# LRA_FlightComputerV.net
KiCad netlist of a schematic drawn in EAGLE
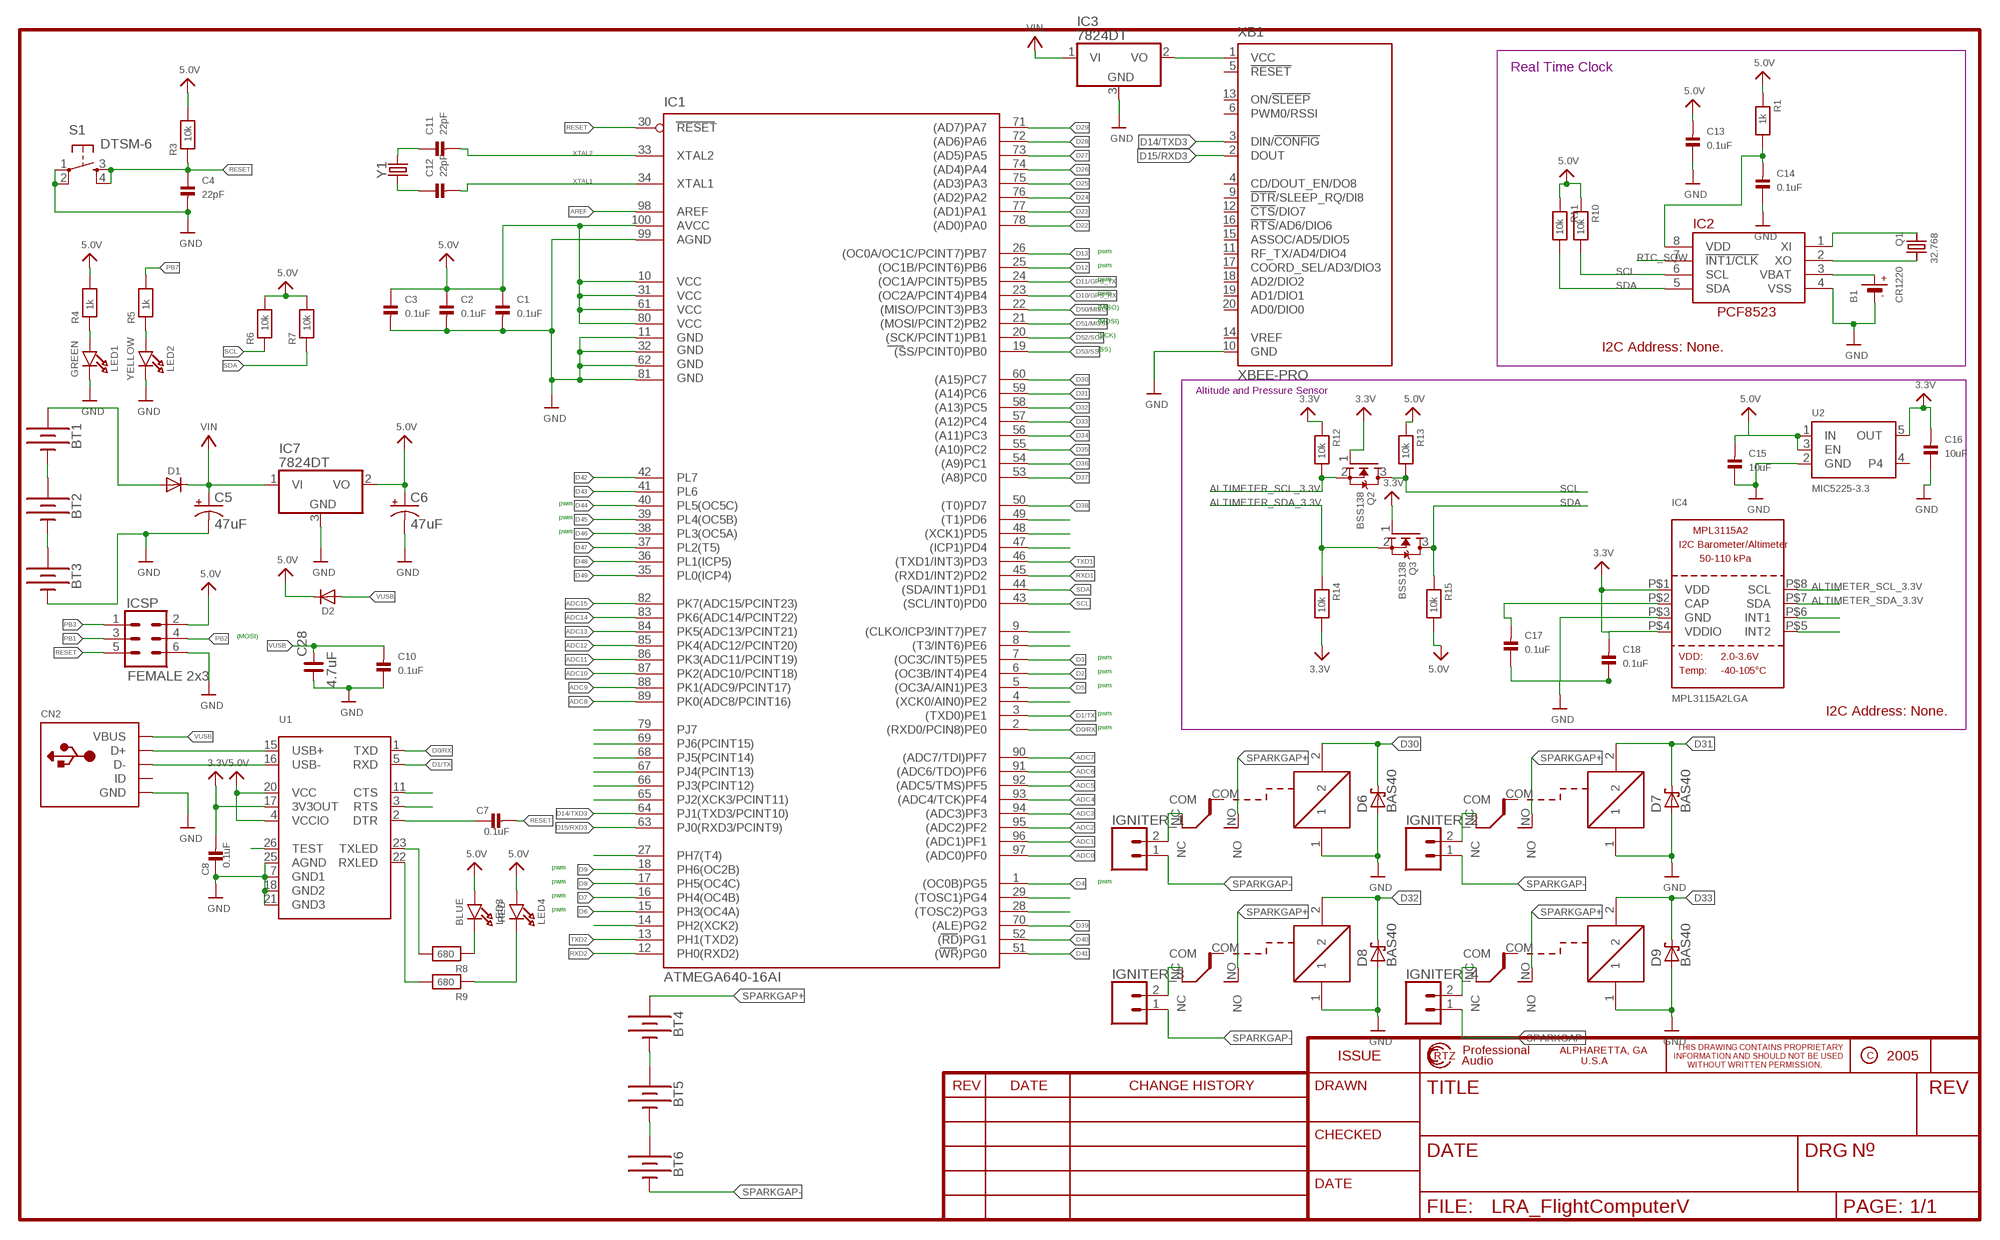
[diagram p0: schematic, sheet 1, part 1 of 2]
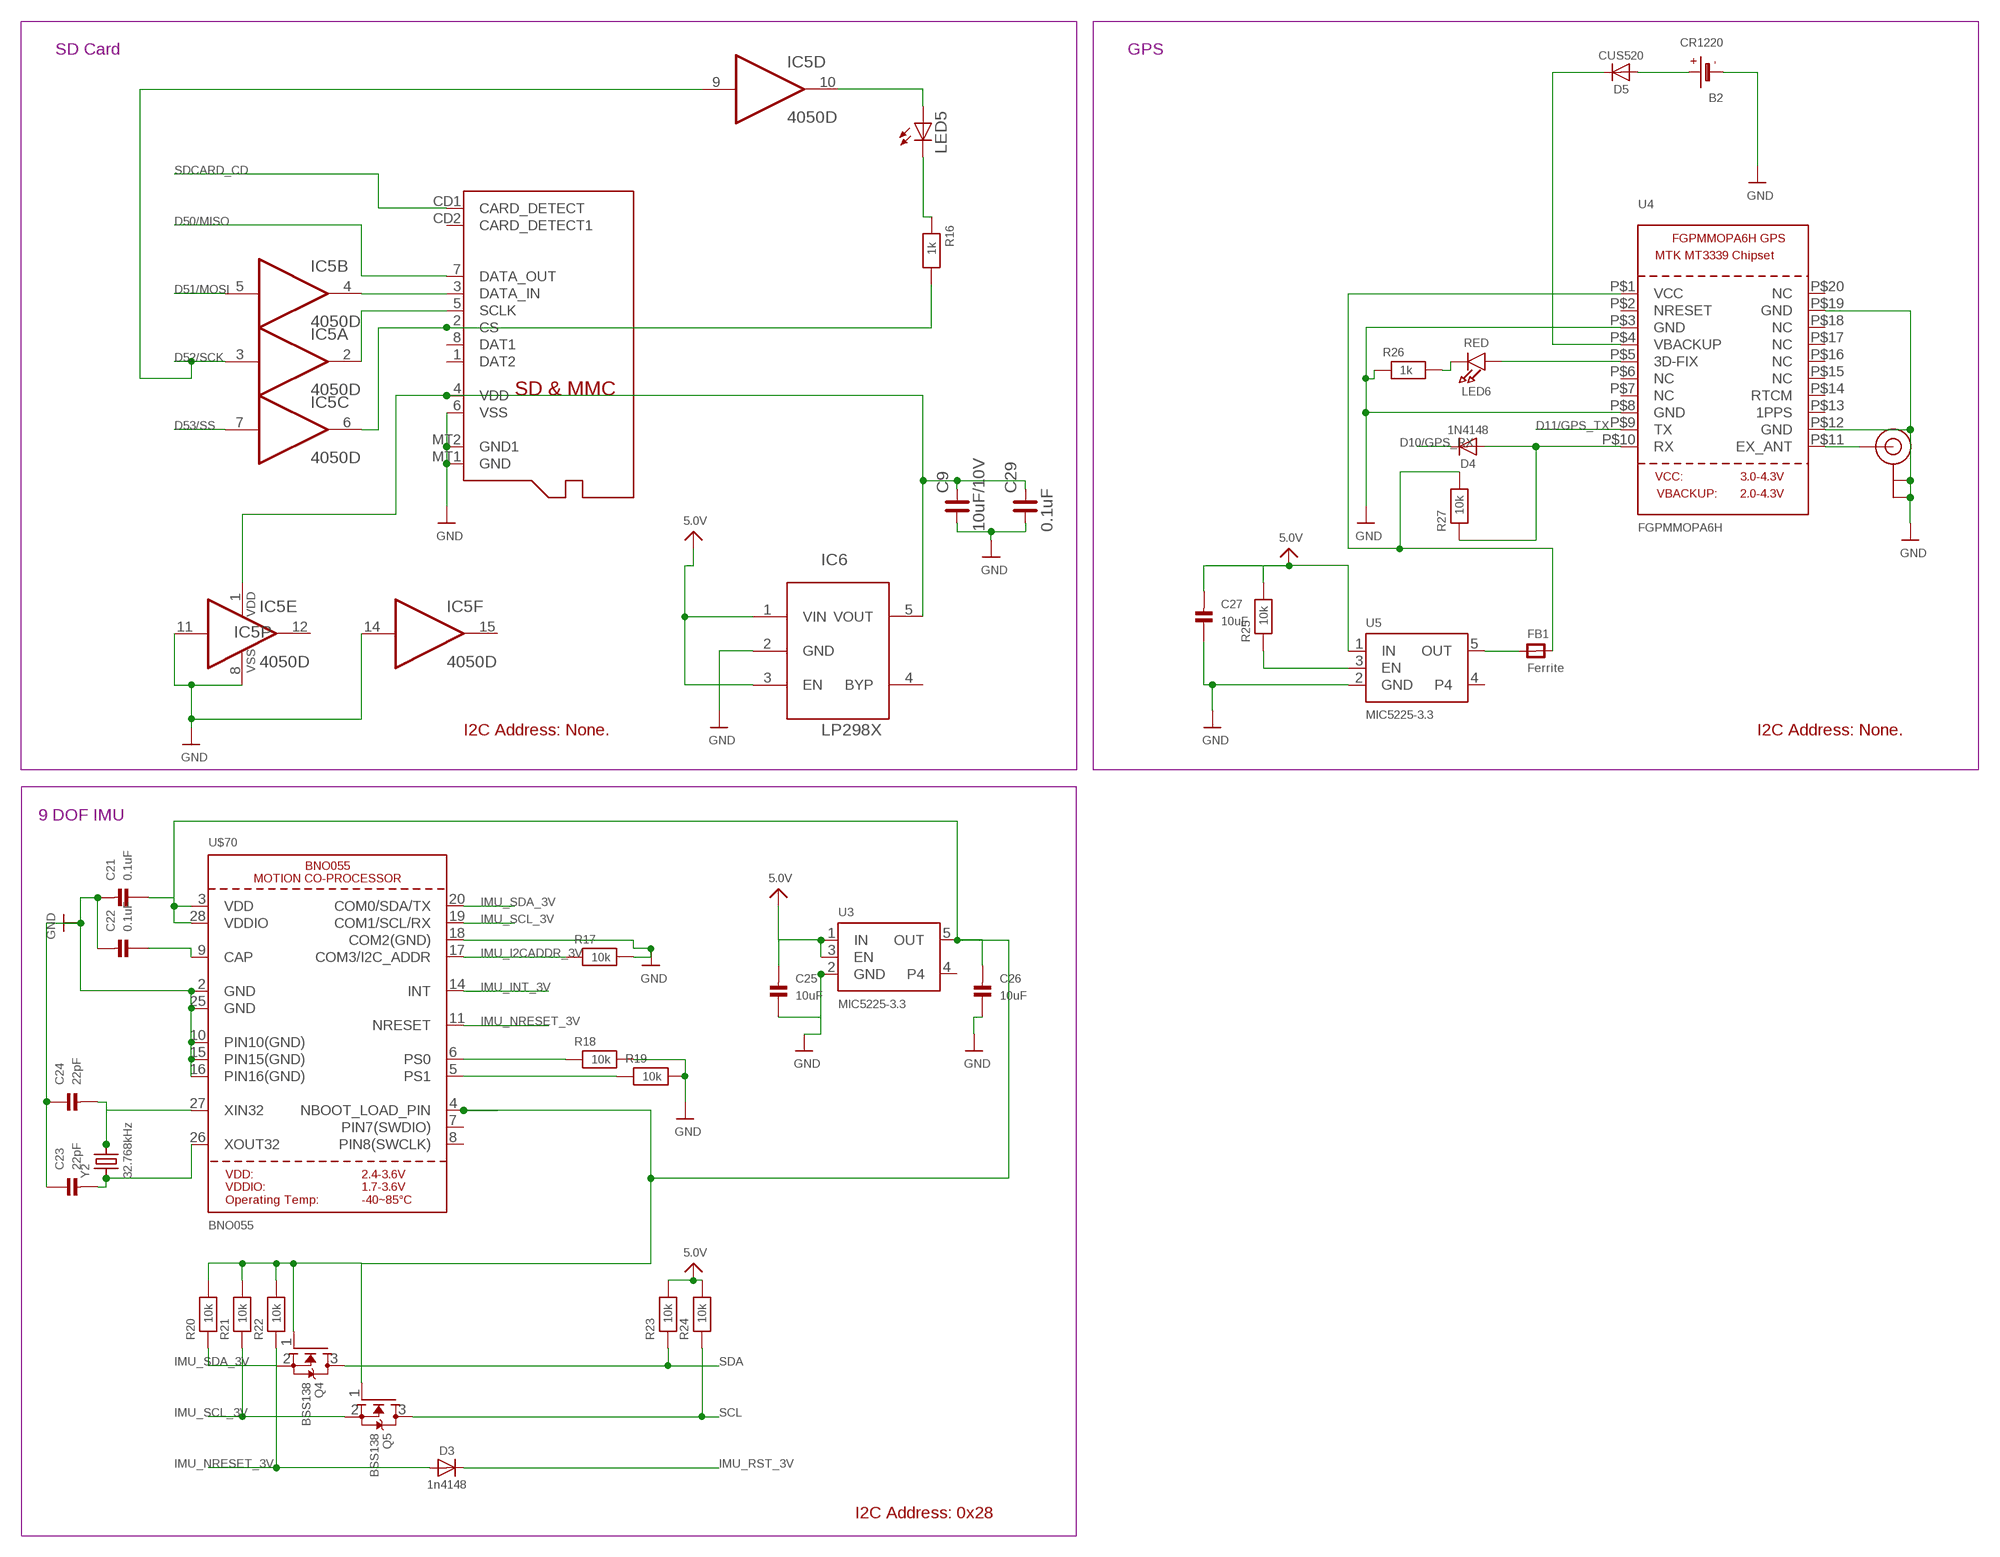
[diagram p1: schematic, sheet 1, part 2 of 2]

(export (version "E")
  (design (tool "Eeschema 10.0.6"))
  (components
    (comp (ref "B1")
      (value "CR1220")
      (footprint "eagle-import:CR1220")
      (libsource (lib "eagle-import") (part "BATTERYCR1220_SMT"))
    )
    (comp (ref "B2")
      (value "CR1220")
      (footprint "eagle-import:CR1220")
      (libsource (lib "eagle-import") (part "BATTERYCR1220_SMT"))
    )
    (comp (ref "BT1")
      (value "BATTERY-18650")
      (footprint "eagle-import:BATTERY_18650-HOLDER")
      (libsource (lib "eagle-import") (part "BATTERY-18650"))
    )
    (comp (ref "BT2")
      (value "BATTERY-18650")
      (footprint "eagle-import:BATTERY_18650-HOLDER")
      (libsource (lib "eagle-import") (part "BATTERY-18650"))
    )
    (comp (ref "BT3")
      (value "BATTERY-18650")
      (footprint "eagle-import:BATTERY_18650-HOLDER")
      (libsource (lib "eagle-import") (part "BATTERY-18650"))
    )
    (comp (ref "BT4")
      (value "BATTERY-18650")
      (footprint "eagle-import:BATTERY_18650-HOLDER")
      (libsource (lib "eagle-import") (part "BATTERY-18650"))
    )
    (comp (ref "BT5")
      (value "BATTERY-18650")
      (footprint "eagle-import:BATTERY_18650-HOLDER")
      (libsource (lib "eagle-import") (part "BATTERY-18650"))
    )
    (comp (ref "BT6")
      (value "BATTERY-18650")
      (footprint "eagle-import:BATTERY_18650-HOLDER")
      (libsource (lib "eagle-import") (part "BATTERY-18650"))
    )
    (comp (ref "C1")
      (value "0.1uF")
      (footprint "eagle-import:0805@1")
      (libsource (lib "eagle-import") (part "CAP_CERAMIC0805"))
    )
    (comp (ref "C2")
      (value "0.1uF")
      (footprint "eagle-import:0805@1")
      (libsource (lib "eagle-import") (part "CAP_CERAMIC0805"))
    )
    (comp (ref "C3")
      (value "0.1uF")
      (footprint "eagle-import:0805@1")
      (libsource (lib "eagle-import") (part "CAP_CERAMIC0805"))
    )
    (comp (ref "C4")
      (value "22pF")
      (footprint "eagle-import:0805@1")
      (libsource (lib "eagle-import") (part "CAP_CERAMIC0805"))
    )
    (comp (ref "C5")
      (value "47uF")
      (footprint "eagle-import:PANASONIC_D")
      (libsource (lib "eagle-import") (part "CPOL-USD"))
    )
    (comp (ref "C6")
      (value "47uF")
      (footprint "eagle-import:PANASONIC_D")
      (libsource (lib "eagle-import") (part "CPOL-USD"))
    )
    (comp (ref "C7")
      (value "0.1uF")
      (footprint "eagle-import:0805@1")
      (libsource (lib "eagle-import") (part "CAP_CERAMIC0805"))
    )
    (comp (ref "C8")
      (value "0.1uF")
      (footprint "eagle-import:0805@1")
      (libsource (lib "eagle-import") (part "CAP_CERAMIC0805"))
    )
    (comp (ref "C9")
      (value "10uF/10V")
      (footprint "eagle-import:C0805")
      (libsource (lib "eagle-import") (part "C_0805"))
    )
    (comp (ref "C10")
      (value "0.1uF")
      (footprint "eagle-import:0805@1")
      (libsource (lib "eagle-import") (part "CAP_CERAMIC0805"))
    )
    (comp (ref "C11")
      (value "22pF")
      (footprint "eagle-import:0805@1")
      (libsource (lib "eagle-import") (part "CAP_CERAMIC0805"))
    )
    (comp (ref "C12")
      (value "22pF")
      (footprint "eagle-import:0805@1")
      (libsource (lib "eagle-import") (part "CAP_CERAMIC0805"))
    )
    (comp (ref "C13")
      (value "0.1uF")
      (footprint "eagle-import:0805@1")
      (libsource (lib "eagle-import") (part "CAP_CERAMIC0805"))
    )
    (comp (ref "C14")
      (value "0.1uF")
      (footprint "eagle-import:0805@1")
      (libsource (lib "eagle-import") (part "CAP_CERAMIC0805"))
    )
    (comp (ref "C15")
      (value "10uF")
      (footprint "eagle-import:0805@1")
      (libsource (lib "eagle-import") (part "CAP_CERAMIC0805"))
    )
    (comp (ref "C16")
      (value "10uF")
      (footprint "eagle-import:0805@1")
      (libsource (lib "eagle-import") (part "CAP_CERAMIC0805"))
    )
    (comp (ref "C17")
      (value "0.1uF")
      (footprint "eagle-import:0805@1")
      (libsource (lib "eagle-import") (part "CAP_CERAMIC0805"))
    )
    (comp (ref "C18")
      (value "0.1uF")
      (footprint "eagle-import:0805@1")
      (libsource (lib "eagle-import") (part "CAP_CERAMIC0805"))
    )
    (comp (ref "C21")
      (value "0.1uF")
      (footprint "eagle-import:0805@1")
      (libsource (lib "eagle-import") (part "CAP_CERAMIC0805"))
    )
    (comp (ref "C22")
      (value "0.1uF")
      (footprint "eagle-import:0805@1")
      (libsource (lib "eagle-import") (part "CAP_CERAMIC0805"))
    )
    (comp (ref "C23")
      (value "22pF")
      (footprint "eagle-import:0805@1")
      (libsource (lib "eagle-import") (part "CAP_CERAMIC0805"))
    )
    (comp (ref "C24")
      (value "22pF")
      (footprint "eagle-import:0805@1")
      (libsource (lib "eagle-import") (part "CAP_CERAMIC0805"))
    )
    (comp (ref "C25")
      (value "10uF")
      (footprint "eagle-import:0805@1")
      (libsource (lib "eagle-import") (part "CAP_CERAMIC0805"))
    )
    (comp (ref "C26")
      (value "10uF")
      (footprint "eagle-import:0805@1")
      (libsource (lib "eagle-import") (part "CAP_CERAMIC0805"))
    )
    (comp (ref "C27")
      (value "10uF")
      (footprint "eagle-import:0805@1")
      (libsource (lib "eagle-import") (part "CAP_CERAMIC0805"))
    )
    (comp (ref "C28")
      (value "4.7uF")
      (footprint "eagle-import:C0805")
      (libsource (lib "eagle-import") (part "C_0805"))
    )
    (comp (ref "C29")
      (value "0.1uF")
      (footprint "eagle-import:C0805")
      (libsource (lib "eagle-import") (part "C_0805"))
    )
    (comp (ref "CN2")
      (value "USBMINIB")
      (footprint "eagle-import:USB-MINIB")
      (libsource (lib "eagle-import") (part "USBMINIB"))
    )
    (comp (ref "D1")
      (value "DIODESOD-123")
      (footprint "eagle-import:SOD-123")
      (libsource (lib "eagle-import") (part "DIODESOD-123"))
    )
    (comp (ref "D2")
      (value "DIODESOD-123")
      (footprint "eagle-import:SOD-123")
      (libsource (lib "eagle-import") (part "DIODESOD-123"))
    )
    (comp (ref "D3")
      (value "1n4148")
      (footprint "eagle-import:SOD-323")
      (libsource (lib "eagle-import") (part "DIODESOD-323"))
    )
    (comp (ref "D4")
      (value "1N4148")
      (footprint "eagle-import:SOD-323")
      (libsource (lib "eagle-import") (part "DIODESOD-323"))
    )
    (comp (ref "D5")
      (value "CUS520")
      (footprint "eagle-import:SOD-323")
      (libsource (lib "eagle-import") (part "DIODESOD-323"))
    )
    (comp (ref "D6")
      (value "BAS40")
      (footprint "eagle-import:SOT23")
      (libsource (lib "eagle-import") (part "BAS40"))
    )
    (comp (ref "D7")
      (value "BAS40")
      (footprint "eagle-import:SOT23")
      (libsource (lib "eagle-import") (part "BAS40"))
    )
    (comp (ref "D8")
      (value "BAS40")
      (footprint "eagle-import:SOT23")
      (libsource (lib "eagle-import") (part "BAS40"))
    )
    (comp (ref "D9")
      (value "BAS40")
      (footprint "eagle-import:SOT23")
      (libsource (lib "eagle-import") (part "BAS40"))
    )
    (comp (ref "FB1")
      (value "Ferrite")
      (footprint "eagle-import:0805-NO")
      (libsource (lib "eagle-import") (part "FERRITE-0805NO"))
    )
    (comp (ref "IC1")
      (value "ATMEGA640-16AI")
      (footprint "eagle-import:TQFP100")
      (libsource (lib "eagle-import") (part "ATMEGAAI640-16"))
    )
    (comp (ref "IC2")
      (value "RTC_PCF8523T")
      (footprint "eagle-import:SOIC8_150MIL")
      (libsource (lib "eagle-import") (part "RTC_PCF8523T"))
    )
    (comp (ref "IC3")
      (value "7824DT")
      (footprint "eagle-import:TO252")
      (libsource (lib "eagle-import") (part "78DT24"))
    )
    (comp (ref "IC4")
      (value "MPL3115A2LGA")
      (footprint "eagle-import:LGA8")
      (libsource (lib "eagle-import") (part "MPL3115A2LGA"))
    )
    (comp (ref "IC5")
      (value "4050D")
      (footprint "eagle-import:SO16")
      (libsource (lib "eagle-import") (part "4050D"))
    )
    (comp (ref "IC6")
      (value "LP298XS")
      (footprint "eagle-import:SOT23-5L")
      (libsource (lib "eagle-import") (part "LP298XS"))
    )
    (comp (ref "IC7")
      (value "7824DT")
      (footprint "eagle-import:TO252")
      (libsource (lib "eagle-import") (part "78DT24"))
    )
    (comp (ref "ICSP")
      (value "FEMALE 2x3")
      (footprint "eagle-import:2X3")
      (libsource (lib "eagle-import") (part "CONN_03X2FEMALE"))
    )
    (comp (ref "IGNITER_1")
      (value "CONN_02")
      (footprint "eagle-import:1X02")
      (libsource (lib "eagle-import") (part "CONN_02"))
    )
    (comp (ref "IGNITER_2")
      (value "CONN_02")
      (footprint "eagle-import:1X02")
      (libsource (lib "eagle-import") (part "CONN_02"))
    )
    (comp (ref "IGNITER_3")
      (value "CONN_02")
      (footprint "eagle-import:1X02")
      (libsource (lib "eagle-import") (part "CONN_02"))
    )
    (comp (ref "IGNITER_4")
      (value "CONN_02")
      (footprint "eagle-import:1X02")
      (libsource (lib "eagle-import") (part "CONN_02"))
    )
    (comp (ref "LED1")
      (value "GREEN")
      (footprint "eagle-import:CHIPLED_0805")
      (libsource (lib "eagle-import") (part "LED0805"))
    )
    (comp (ref "LED2")
      (value "YELLOW")
      (footprint "eagle-import:CHIPLED_0805")
      (libsource (lib "eagle-import") (part "LED0805"))
    )
    (comp (ref "LED3")
      (value "BLUE")
      (footprint "eagle-import:CHIPLED_0805")
      (libsource (lib "eagle-import") (part "LED0805"))
    )
    (comp (ref "LED4")
      (value "RED")
      (footprint "eagle-import:CHIPLED_0805")
      (libsource (lib "eagle-import") (part "LED0805"))
    )
    (comp (ref "LED5")
      (value "LEDCHIPLED_0805")
      (footprint "eagle-import:CHIPLED_0805")
      (libsource (lib "eagle-import") (part "LEDCHIPLED_0805"))
    )
    (comp (ref "LED6")
      (value "RED")
      (footprint "eagle-import:CHIPLED_0805")
      (libsource (lib "eagle-import") (part "LED0805"))
    )
    (comp (ref "Q1")
      (value "32.768")
      (footprint "eagle-import:CRYSTAL_8X3.8")
      (libsource (lib "eagle-import") (part "CRYSTAL8.0X3.8"))
    )
    (comp (ref "Q2")
      (value "BSS138")
      (footprint "eagle-import:SOT23-WIDE")
      (libsource (lib "eagle-import") (part "MOSFET-NWIDE"))
    )
    (comp (ref "Q3")
      (value "BSS138")
      (footprint "eagle-import:SOT23-WIDE")
      (libsource (lib "eagle-import") (part "MOSFET-NWIDE"))
    )
    (comp (ref "Q4")
      (value "BSS138")
      (footprint "eagle-import:SOT23-WIDE")
      (libsource (lib "eagle-import") (part "MOSFET-NWIDE"))
    )
    (comp (ref "Q5")
      (value "BSS138")
      (footprint "eagle-import:SOT23-WIDE")
      (libsource (lib "eagle-import") (part "MOSFET-NWIDE"))
    )
    (comp (ref "R1")
      (value "1k")
      (footprint "eagle-import:0805@1")
      (libsource (lib "eagle-import") (part "RESISTOR0805"))
    )
    (comp (ref "R3")
      (value "10k")
      (footprint "eagle-import:0805@1")
      (libsource (lib "eagle-import") (part "RESISTOR0805"))
    )
    (comp (ref "R4")
      (value "1k")
      (footprint "eagle-import:0805@1")
      (libsource (lib "eagle-import") (part "RESISTOR0805"))
    )
    (comp (ref "R5")
      (value "1k")
      (footprint "eagle-import:0805@1")
      (libsource (lib "eagle-import") (part "RESISTOR0805"))
    )
    (comp (ref "R6")
      (value "10k")
      (footprint "eagle-import:0805@1")
      (libsource (lib "eagle-import") (part "RESISTOR0805"))
    )
    (comp (ref "R7")
      (value "10k")
      (footprint "eagle-import:0805@1")
      (libsource (lib "eagle-import") (part "RESISTOR0805"))
    )
    (comp (ref "R8")
      (value "680")
      (footprint "eagle-import:0805@1")
      (libsource (lib "eagle-import") (part "RESISTOR0805"))
    )
    (comp (ref "R9")
      (value "680")
      (footprint "eagle-import:0805@1")
      (libsource (lib "eagle-import") (part "RESISTOR0805"))
    )
    (comp (ref "R10")
      (value "10k")
      (footprint "eagle-import:0805@1")
      (libsource (lib "eagle-import") (part "RESISTOR0805"))
    )
    (comp (ref "R11")
      (value "10k")
      (footprint "eagle-import:0805@1")
      (libsource (lib "eagle-import") (part "RESISTOR0805"))
    )
    (comp (ref "R12")
      (value "10k")
      (footprint "eagle-import:0805@1")
      (libsource (lib "eagle-import") (part "RESISTOR0805"))
    )
    (comp (ref "R13")
      (value "10k")
      (footprint "eagle-import:0805@1")
      (libsource (lib "eagle-import") (part "RESISTOR0805"))
    )
    (comp (ref "R14")
      (value "10k")
      (footprint "eagle-import:0805@1")
      (libsource (lib "eagle-import") (part "RESISTOR0805"))
    )
    (comp (ref "R15")
      (value "10k")
      (footprint "eagle-import:0805@1")
      (libsource (lib "eagle-import") (part "RESISTOR0805"))
    )
    (comp (ref "R16")
      (value "1k")
      (footprint "eagle-import:0805@1")
      (libsource (lib "eagle-import") (part "RESISTOR0805"))
    )
    (comp (ref "R17")
      (value "10k")
      (footprint "eagle-import:0805@1")
      (libsource (lib "eagle-import") (part "RESISTOR0805"))
    )
    (comp (ref "R18")
      (value "10k")
      (footprint "eagle-import:0805@1")
      (libsource (lib "eagle-import") (part "RESISTOR0805"))
    )
    (comp (ref "R19")
      (value "10k")
      (footprint "eagle-import:0805@1")
      (libsource (lib "eagle-import") (part "RESISTOR0805"))
    )
    (comp (ref "R20")
      (value "10k")
      (footprint "eagle-import:0805@1")
      (libsource (lib "eagle-import") (part "RESISTOR0805"))
    )
    (comp (ref "R21")
      (value "10k")
      (footprint "eagle-import:0805@1")
      (libsource (lib "eagle-import") (part "RESISTOR0805"))
    )
    (comp (ref "R22")
      (value "10k")
      (footprint "eagle-import:0805@1")
      (libsource (lib "eagle-import") (part "RESISTOR0805"))
    )
    (comp (ref "R23")
      (value "10k")
      (footprint "eagle-import:0805@1")
      (libsource (lib "eagle-import") (part "RESISTOR0805"))
    )
    (comp (ref "R24")
      (value "10k")
      (footprint "eagle-import:0805@1")
      (libsource (lib "eagle-import") (part "RESISTOR0805"))
    )
    (comp (ref "R25")
      (value "10k")
      (footprint "eagle-import:0805@1")
      (libsource (lib "eagle-import") (part "RESISTOR0805"))
    )
    (comp (ref "R26")
      (value "1k")
      (footprint "eagle-import:0805@1")
      (libsource (lib "eagle-import") (part "RESISTOR0805"))
    )
    (comp (ref "R27")
      (value "10k")
      (footprint "eagle-import:0805@1")
      (libsource (lib "eagle-import") (part "RESISTOR0805"))
    )
    (comp (ref "S1")
      (value "DTSM-6")
      (footprint "eagle-import:DTSM-6")
      (libsource (lib "eagle-import") (part "DTSM-6"))
    )
    (comp (ref "U$70")
      (value "BNO055")
      (footprint "eagle-import:BNO055")
      (libsource (lib "eagle-import") (part "BNO055"))
    )
    (comp (ref "U$78")
      (value "U.FL")
      (footprint "eagle-import:U.FL")
      (libsource (lib "eagle-import") (part "U.FL"))
    )
    (comp (ref "U$84")
      (value "RW-SH")
      (footprint "eagle-import:RW-SH")
      (libsource (lib "eagle-import") (part "RW-SH"))
    )
    (comp (ref "U$86")
      (value "RW-SH")
      (footprint "eagle-import:RW-SH")
      (libsource (lib "eagle-import") (part "RW-SH"))
    )
    (comp (ref "U$87")
      (value "RW-SH")
      (footprint "eagle-import:RW-SH")
      (libsource (lib "eagle-import") (part "RW-SH"))
    )
    (comp (ref "U$90")
      (value "RW-SH")
      (footprint "eagle-import:RW-SH")
      (libsource (lib "eagle-import") (part "RW-SH"))
    )
    (comp (ref "U1")
      (value "FT232RLSSOP28")
      (footprint "eagle-import:SSOP28DB")
      (libsource (lib "eagle-import") (part "FT232RLSSOP28"))
    )
    (comp (ref "U2")
      (value "MIC5225-3.3")
      (footprint "eagle-import:SOT23-5")
      (libsource (lib "eagle-import") (part "VREG_SOT23-5"))
    )
    (comp (ref "U3")
      (value "MIC5225-3.3")
      (footprint "eagle-import:SOT23-5")
      (libsource (lib "eagle-import") (part "VREG_SOT23-5"))
    )
    (comp (ref "U4")
      (value "FGPMMOPA6H")
      (footprint "eagle-import:FGPMMOPA6H")
      (libsource (lib "eagle-import") (part "GPS_FGPMMOPA6H"))
    )
    (comp (ref "U5")
      (value "MIC5225-3.3")
      (footprint "eagle-import:SOT23-5")
      (libsource (lib "eagle-import") (part "VREG_SOT23-5"))
    )
    (comp (ref "X1")
      (value "MICROSD")
      (footprint "eagle-import:MICROSD")
      (libsource (lib "eagle-import") (part "MICROSD"))
    )
    (comp (ref "XB1")
      (value "XBEE-PRO")
      (footprint "eagle-import:XBEE-PRO")
      (fields (field (name "MPN") "XBP24-AWI-001"))
      (libsource (lib "eagle-import") (part "XBEE-PRO"))
    )
    (comp (ref "Y1")
      (value "CRYSTALPTH-HC49US")
      (footprint "eagle-import:HC49US")
      (libsource (lib "eagle-import") (part "CRYSTALPTH-HC49US"))
    )
    (comp (ref "Y2")
      (value "32.768kHz")
      (footprint "eagle-import:CRYSTAL_8X3.8")
      (libsource (lib "eagle-import") (part "CRYSTAL8.0X3.8"))
    )
  )
  (nets
    (net (code "1") (name "/ALTIMETER_SCL_3.3V") (class "Default")
      (node (ref "IC4") (pin "P$8") (pinfunction "SCL_P$8") (pintype "bidirectional"))
      (node (ref "Q2") (pin "2") (pinfunction "S_2") (pintype "bidirectional"))
      (node (ref "R12") (pin "2") (pinfunction "2_2") (pintype "passive"))
    )
    (net (code "2") (name "/ALTIMETER_SDA_3.3V") (class "Default")
      (node (ref "IC4") (pin "P$7") (pinfunction "SDA_P$7") (pintype "bidirectional"))
      (node (ref "Q3") (pin "2") (pinfunction "S_2") (pintype "bidirectional"))
      (node (ref "R14") (pin "1") (pinfunction "1_1") (pintype "passive"))
    )
    (net (code "3") (name "/IMU_I2CADDR_3V") (class "Default")
      (node (ref "R17") (pin "1") (pinfunction "1_1") (pintype "passive"))
      (node (ref "U$70") (pin "17") (pinfunction "COM3/I2C_ADDR_17") (pintype "bidirectional"))
    )
    (net (code "4") (name "/IMU_INT_3V") (class "Default")
      (node (ref "U$70") (pin "14") (pinfunction "INT_14") (pintype "output"))
    )
    (net (code "5") (name "/IMU_NRESET_3V") (class "Default")
      (node (ref "D3") (pin "A") (pinfunction "A_A") (pintype "passive"))
      (node (ref "R22") (pin "1") (pinfunction "1_1") (pintype "passive"))
      (node (ref "U$70") (pin "11") (pinfunction "NRESET_11") (pintype "bidirectional"))
    )
    (net (code "6") (name "/IMU_RST_3V") (class "Default")
      (node (ref "D3") (pin "C") (pinfunction "C_C") (pintype "passive"))
    )
    (net (code "7") (name "/IMU_SCL_3V") (class "Default")
      (node (ref "Q5") (pin "2") (pinfunction "S_2") (pintype "bidirectional"))
      (node (ref "R21") (pin "1") (pinfunction "1_1") (pintype "passive"))
      (node (ref "U$70") (pin "19") (pinfunction "COM1/SCL/RX_19") (pintype "bidirectional"))
    )
    (net (code "8") (name "/IMU_SDA_3V") (class "Default")
      (node (ref "Q4") (pin "2") (pinfunction "S_2") (pintype "bidirectional"))
      (node (ref "R20") (pin "1") (pinfunction "1_1") (pintype "passive"))
      (node (ref "U$70") (pin "20") (pinfunction "COM0/SDA/TX_20") (pintype "bidirectional"))
    )
    (net (code "9") (name "/OUT") (class "Default")
      (node (ref "C21") (pin "1") (pinfunction "P$1_1") (pintype "passive"))
      (node (ref "C26") (pin "2") (pinfunction "P$2_2") (pintype "passive"))
      (node (ref "FB1") (pin "1") (pinfunction "P$1_1") (pintype "passive"))
      (node (ref "Q4") (pin "1") (pinfunction "G_1") (pintype "bidirectional"))
      (node (ref "Q5") (pin "1") (pinfunction "G_1") (pintype "bidirectional"))
      (node (ref "R20") (pin "2") (pinfunction "2_2") (pintype "passive"))
      (node (ref "R21") (pin "2") (pinfunction "2_2") (pintype "passive"))
      (node (ref "R22") (pin "2") (pinfunction "2_2") (pintype "passive"))
      (node (ref "U$70") (pin "28") (pinfunction "VDDIO_28") (pintype "power_in"))
      (node (ref "U$70") (pin "3") (pinfunction "VDD_3") (pintype "power_in"))
      (node (ref "U$70") (pin "4") (pinfunction "NBOOT_LOAD_PIN_4") (pintype "bidirectional"))
      (node (ref "U3") (pin "5") (pinfunction "OUT_5") (pintype "power_in"))
      (node (ref "U5") (pin "5") (pinfunction "OUT_5") (pintype "power_in"))
    )
    (net (code "10") (name "/RTC_SQW") (class "Default")
      (node (ref "IC2") (pin "7") (pinfunction "~{INT1/CLK}_7") (pintype "output"))
    )
    (net (code "11") (name "/SDCARD_CD") (class "Default")
      (node (ref "X1") (pin "CD1") (pinfunction "CARD_DETECT_CD1") (pintype "passive"))
    )
    (net (code "12") (name "/XTAL1") (class "Default")
      (node (ref "C12") (pin "2") (pinfunction "P$2_2") (pintype "passive"))
      (node (ref "IC1") (pin "34") (pinfunction "XTAL1_34") (pintype "input"))
    )
    (net (code "13") (name "/XTAL2") (class "Default")
      (node (ref "C11") (pin "2") (pinfunction "P$2_2") (pintype "passive"))
      (node (ref "IC1") (pin "33") (pinfunction "XTAL2_33") (pintype "output"))
    )
    (net (code "14") (name "3.3V") (class "Default")
      (node (ref "C16") (pin "2") (pinfunction "P$2_2") (pintype "passive"))
      (node (ref "C18") (pin "2") (pinfunction "P$2_2") (pintype "passive"))
      (node (ref "C8") (pin "2") (pinfunction "P$2_2") (pintype "passive"))
      (node (ref "IC4") (pin "P$1") (pinfunction "VDD_P$1") (pintype "power_in"))
      (node (ref "IC4") (pin "P$4") (pinfunction "VDDIO_P$4") (pintype "power_in"))
      (node (ref "Q2") (pin "1") (pinfunction "G_1") (pintype "bidirectional"))
      (node (ref "Q3") (pin "1") (pinfunction "G_1") (pintype "bidirectional"))
      (node (ref "R12") (pin "1") (pinfunction "1_1") (pintype "passive"))
      (node (ref "R14") (pin "2") (pinfunction "2_2") (pintype "passive"))
      (node (ref "U1") (pin "17") (pinfunction "3V3OUT_17") (pintype "power_in"))
      (node (ref "U2") (pin "5") (pinfunction "OUT_5") (pintype "power_in"))
    )
    (net (code "15") (name "5.0V") (class "Default")
      (node (ref "C1") (pin "1") (pinfunction "P$1_1") (pintype "passive"))
      (node (ref "C13") (pin "2") (pinfunction "P$2_2") (pintype "passive"))
      (node (ref "C15") (pin "2") (pinfunction "P$2_2") (pintype "passive"))
      (node (ref "C2") (pin "1") (pinfunction "P$1_1") (pintype "passive"))
      (node (ref "C25") (pin "2") (pinfunction "P$2_2") (pintype "passive"))
      (node (ref "C27") (pin "2") (pinfunction "P$2_2") (pintype "passive"))
      (node (ref "C3") (pin "1") (pinfunction "P$1_1") (pintype "passive"))
      (node (ref "C6") (pin "+") (pinfunction "+_+") (pintype "passive"))
      (node (ref "D2") (pin "C") (pinfunction "C_C") (pintype "passive"))
      (node (ref "IC1") (pin "10") (pinfunction "VCC_10") (pintype "power_in"))
      (node (ref "IC1") (pin "100") (pinfunction "AVCC_100") (pintype "power_in"))
      (node (ref "IC1") (pin "31") (pinfunction "VCC1_31") (pintype "power_in"))
      (node (ref "IC1") (pin "61") (pinfunction "VCC2_61") (pintype "power_in"))
      (node (ref "IC1") (pin "80") (pinfunction "VCC3_80") (pintype "power_in"))
      (node (ref "IC6") (pin "1") (pinfunction "VIN_1") (pintype "bidirectional"))
      (node (ref "IC6") (pin "3") (pinfunction "EN_3") (pintype "bidirectional"))
      (node (ref "IC7") (pin "2") (pinfunction "VO_2") (pintype "passive"))
      (node (ref "ICSP") (pin "2") (pinfunction "2_2") (pintype "bidirectional"))
      (node (ref "LED3") (pin "A") (pinfunction "A_A") (pintype "passive"))
      (node (ref "LED4") (pin "A") (pinfunction "A_A") (pintype "passive"))
      (node (ref "R1") (pin "1") (pinfunction "1_1") (pintype "passive"))
      (node (ref "R10") (pin "1") (pinfunction "1_1") (pintype "passive"))
      (node (ref "R11") (pin "1") (pinfunction "1_1") (pintype "passive"))
      (node (ref "R13") (pin "1") (pinfunction "1_1") (pintype "passive"))
      (node (ref "R15") (pin "2") (pinfunction "2_2") (pintype "passive"))
      (node (ref "R23") (pin "2") (pinfunction "2_2") (pintype "passive"))
      (node (ref "R24") (pin "2") (pinfunction "2_2") (pintype "passive"))
      (node (ref "R25") (pin "2") (pinfunction "2_2") (pintype "passive"))
      (node (ref "R3") (pin "2") (pinfunction "2_2") (pintype "passive"))
      (node (ref "R4") (pin "2") (pinfunction "2_2") (pintype "passive"))
      (node (ref "R6") (pin "2") (pinfunction "2_2") (pintype "passive"))
      (node (ref "R7") (pin "2") (pinfunction "2_2") (pintype "passive"))
      (node (ref "U1") (pin "20") (pinfunction "VCC_20") (pintype "power_in"))
      (node (ref "U1") (pin "4") (pinfunction "VCCIO_4") (pintype "power_in"))
      (node (ref "U2") (pin "1") (pinfunction "IN_1") (pintype "power_in"))
      (node (ref "U2") (pin "3") (pinfunction "EN_3") (pintype "input"))
      (node (ref "U3") (pin "1") (pinfunction "IN_1") (pintype "power_in"))
      (node (ref "U3") (pin "3") (pinfunction "EN_3") (pintype "input"))
      (node (ref "U5") (pin "1") (pinfunction "IN_1") (pintype "power_in"))
    )
    (net (code "16") (name "ADC0") (class "Default")
      (node (ref "IC1") (pin "97") (pinfunction "(ADC0)PF0_97") (pintype "bidirectional"))
    )
    (net (code "17") (name "ADC1") (class "Default")
      (node (ref "IC1") (pin "96") (pinfunction "(ADC1)PF1_96") (pintype "bidirectional"))
    )
    (net (code "18") (name "ADC2") (class "Default")
      (node (ref "IC1") (pin "95") (pinfunction "(ADC2)PF2_95") (pintype "bidirectional"))
    )
    (net (code "19") (name "ADC3") (class "Default")
      (node (ref "IC1") (pin "94") (pinfunction "(ADC3)PF3_94") (pintype "bidirectional"))
    )
    (net (code "20") (name "ADC4") (class "Default")
      (node (ref "IC1") (pin "93") (pinfunction "(ADC4/TCK)PF4_93") (pintype "bidirectional"))
    )
    (net (code "21") (name "ADC5") (class "Default")
      (node (ref "IC1") (pin "92") (pinfunction "(ADC5/TMS)PF5_92") (pintype "bidirectional"))
    )
    (net (code "22") (name "ADC6") (class "Default")
      (node (ref "IC1") (pin "91") (pinfunction "(ADC6/TDO)PF6_91") (pintype "bidirectional"))
    )
    (net (code "23") (name "ADC7") (class "Default")
      (node (ref "IC1") (pin "90") (pinfunction "(ADC7/TDI)PF7_90") (pintype "bidirectional"))
    )
    (net (code "24") (name "ADC8") (class "Default")
      (node (ref "IC1") (pin "89") (pinfunction "PK0(ADC8/PCINT16)_89") (pintype "bidirectional"))
    )
    (net (code "25") (name "ADC9") (class "Default")
      (node (ref "IC1") (pin "88") (pinfunction "PK1(ADC9/PCINT17)_88") (pintype "bidirectional"))
    )
    (net (code "26") (name "ADC10") (class "Default")
      (node (ref "IC1") (pin "87") (pinfunction "PK2(ADC10/PCINT18)_87") (pintype "bidirectional"))
    )
    (net (code "27") (name "ADC11") (class "Default")
      (node (ref "IC1") (pin "86") (pinfunction "PK3(ADC11/PCINT19)_86") (pintype "bidirectional"))
    )
    (net (code "28") (name "ADC12") (class "Default")
      (node (ref "IC1") (pin "85") (pinfunction "PK4(ADC12/PCINT20)_85") (pintype "bidirectional"))
    )
    (net (code "29") (name "ADC13") (class "Default")
      (node (ref "IC1") (pin "84") (pinfunction "PK5(ADC13/PCINT21)_84") (pintype "bidirectional"))
    )
    (net (code "30") (name "ADC14") (class "Default")
      (node (ref "IC1") (pin "83") (pinfunction "PK6(ADC14/PCINT22)_83") (pintype "bidirectional"))
    )
    (net (code "31") (name "ADC15") (class "Default")
      (node (ref "IC1") (pin "82") (pinfunction "PK7(ADC15/PCINT23)_82") (pintype "bidirectional"))
    )
    (net (code "32") (name "AREF") (class "Default")
      (node (ref "IC1") (pin "98") (pinfunction "AREF_98") (pintype "bidirectional"))
    )
    (net (code "33") (name "D0{slash}RX") (class "Default")
      (node (ref "IC1") (pin "2") (pinfunction "(RXD0/PCIN8)PE0_2") (pintype "bidirectional"))
      (node (ref "U1") (pin "1") (pinfunction "TXD_1") (pintype "output"))
    )
    (net (code "34") (name "D1{slash}TX") (class "Default")
      (node (ref "IC1") (pin "3") (pinfunction "(TXD0)PE1_3") (pintype "bidirectional"))
      (node (ref "U1") (pin "5") (pinfunction "RXD_5") (pintype "input"))
    )
    (net (code "35") (name "D2") (class "Default")
      (node (ref "IC1") (pin "6") (pinfunction "(OC3B/INT4)PE4_6") (pintype "bidirectional"))
    )
    (net (code "36") (name "D3") (class "Default")
      (node (ref "IC1") (pin "7") (pinfunction "(OC3C/INT5)PE5_7") (pintype "bidirectional"))
    )
    (net (code "37") (name "D4") (class "Default")
      (node (ref "IC1") (pin "1") (pinfunction "(OC0B)PG5_1") (pintype "bidirectional"))
    )
    (net (code "38") (name "D5") (class "Default")
      (node (ref "IC1") (pin "5") (pinfunction "(OC3A/AIN1)PE3_5") (pintype "bidirectional"))
    )
    (net (code "39") (name "D6") (class "Default")
      (node (ref "IC1") (pin "15") (pinfunction "PH3(OC4A)_15") (pintype "bidirectional"))
    )
    (net (code "40") (name "D7") (class "Default")
      (node (ref "IC1") (pin "16") (pinfunction "PH4(OC4B)_16") (pintype "bidirectional"))
    )
    (net (code "41") (name "D8") (class "Default")
      (node (ref "IC1") (pin "17") (pinfunction "PH5(OC4C)_17") (pintype "bidirectional"))
    )
    (net (code "42") (name "D9") (class "Default")
      (node (ref "IC1") (pin "18") (pinfunction "PH6(OC2B)_18") (pintype "bidirectional"))
    )
    (net (code "43") (name "D10{slash}GPS_RX") (class "Default")
      (node (ref "D4") (pin "C") (pinfunction "C_C") (pintype "passive"))
      (node (ref "IC1") (pin "23") (pinfunction "(OC2A/PCINT4)PB4_23") (pintype "bidirectional"))
    )
    (net (code "44") (name "D11{slash}GPS_TX") (class "Default")
      (node (ref "IC1") (pin "24") (pinfunction "(OC1A/PCINT5)PB5_24") (pintype "bidirectional"))
      (node (ref "U4") (pin "P$9") (pinfunction "TX_P$9") (pintype "bidirectional"))
    )
    (net (code "45") (name "D12") (class "Default")
      (node (ref "IC1") (pin "25") (pinfunction "(OC1B/PCINT6)PB6_25") (pintype "bidirectional"))
    )
    (net (code "46") (name "D13") (class "Default")
      (node (ref "IC1") (pin "26") (pinfunction "(OC0A/OC1C/PCINT7)PB7_26") (pintype "bidirectional"))
    )
    (net (code "47") (name "D14{slash}TXD3") (class "Default")
      (node (ref "IC1") (pin "64") (pinfunction "PJ1(TXD3/PCINT10)_64") (pintype "bidirectional"))
      (node (ref "XB1") (pin "3") (pinfunction "DIN/~{CONFIG}_3") (pintype "input"))
    )
    (net (code "48") (name "D15{slash}RXD3") (class "Default")
      (node (ref "IC1") (pin "63") (pinfunction "PJ0(RXD3/PCINT9)_63") (pintype "bidirectional"))
      (node (ref "XB1") (pin "2") (pinfunction "DOUT_2") (pintype "output"))
    )
    (net (code "49") (name "D22") (class "Default")
      (node (ref "IC1") (pin "78") (pinfunction "(AD0)PA0_78") (pintype "bidirectional"))
    )
    (net (code "50") (name "D23") (class "Default")
      (node (ref "IC1") (pin "77") (pinfunction "(AD1)PA1_77") (pintype "bidirectional"))
    )
    (net (code "51") (name "D24") (class "Default")
      (node (ref "IC1") (pin "76") (pinfunction "(AD2)PA2_76") (pintype "bidirectional"))
    )
    (net (code "52") (name "D25") (class "Default")
      (node (ref "IC1") (pin "75") (pinfunction "(AD3)PA3_75") (pintype "bidirectional"))
    )
    (net (code "53") (name "D26") (class "Default")
      (node (ref "IC1") (pin "74") (pinfunction "(AD4)PA4_74") (pintype "bidirectional"))
    )
    (net (code "54") (name "D27") (class "Default")
      (node (ref "IC1") (pin "73") (pinfunction "(AD5)PA5_73") (pintype "bidirectional"))
    )
    (net (code "55") (name "D28") (class "Default")
      (node (ref "IC1") (pin "72") (pinfunction "(AD6)PA6_72") (pintype "bidirectional"))
    )
    (net (code "56") (name "D29") (class "Default")
      (node (ref "IC1") (pin "71") (pinfunction "(AD7)PA7_71") (pintype "bidirectional"))
    )
    (net (code "57") (name "D30") (class "Default")
      (node (ref "D6") (pin "3") (pinfunction "C_3") (pintype "passive"))
      (node (ref "IC1") (pin "60") (pinfunction "(A15)PC7_60") (pintype "bidirectional"))
      (node (ref "U$87") (pin "2") (pinfunction "2_2") (pintype "bidirectional"))
    )
    (net (code "58") (name "D31") (class "Default")
      (node (ref "D7") (pin "3") (pinfunction "C_3") (pintype "passive"))
      (node (ref "IC1") (pin "59") (pinfunction "(A14)PC6_59") (pintype "bidirectional"))
      (node (ref "U$84") (pin "2") (pinfunction "2_2") (pintype "bidirectional"))
    )
    (net (code "59") (name "D32") (class "Default")
      (node (ref "D8") (pin "3") (pinfunction "C_3") (pintype "passive"))
      (node (ref "IC1") (pin "58") (pinfunction "(A13)PC5_58") (pintype "bidirectional"))
      (node (ref "U$86") (pin "2") (pinfunction "2_2") (pintype "bidirectional"))
    )
    (net (code "60") (name "D33") (class "Default")
      (node (ref "D9") (pin "3") (pinfunction "C_3") (pintype "passive"))
      (node (ref "IC1") (pin "57") (pinfunction "(A12)PC4_57") (pintype "bidirectional"))
      (node (ref "U$90") (pin "2") (pinfunction "2_2") (pintype "bidirectional"))
    )
    (net (code "61") (name "D34") (class "Default")
      (node (ref "IC1") (pin "56") (pinfunction "(A11)PC3_56") (pintype "bidirectional"))
    )
    (net (code "62") (name "D35") (class "Default")
      (node (ref "IC1") (pin "55") (pinfunction "(A10)PC2_55") (pintype "bidirectional"))
    )
    (net (code "63") (name "D36") (class "Default")
      (node (ref "IC1") (pin "54") (pinfunction "(A9)PC1_54") (pintype "bidirectional"))
    )
    (net (code "64") (name "D37") (class "Default")
      (node (ref "IC1") (pin "53") (pinfunction "(A8)PC0_53") (pintype "bidirectional"))
    )
    (net (code "65") (name "D38") (class "Default")
      (node (ref "IC1") (pin "50") (pinfunction "(T0)PD7_50") (pintype "bidirectional"))
    )
    (net (code "66") (name "D39") (class "Default")
      (node (ref "IC1") (pin "70") (pinfunction "(ALE)PG2_70") (pintype "bidirectional"))
    )
    (net (code "67") (name "D40") (class "Default")
      (node (ref "IC1") (pin "52") (pinfunction "(RD)PG1_52") (pintype "bidirectional"))
    )
    (net (code "68") (name "D41") (class "Default")
      (node (ref "IC1") (pin "51") (pinfunction "(WR)PG0_51") (pintype "bidirectional"))
    )
    (net (code "69") (name "D42") (class "Default")
      (node (ref "IC1") (pin "42") (pinfunction "PL7_42") (pintype "bidirectional"))
    )
    (net (code "70") (name "D43") (class "Default")
      (node (ref "IC1") (pin "41") (pinfunction "PL6_41") (pintype "bidirectional"))
    )
    (net (code "71") (name "D44") (class "Default")
      (node (ref "IC1") (pin "40") (pinfunction "PL5(OC5C)_40") (pintype "bidirectional"))
    )
    (net (code "72") (name "D45") (class "Default")
      (node (ref "IC1") (pin "39") (pinfunction "PL4(OC5B)_39") (pintype "bidirectional"))
    )
    (net (code "73") (name "D46") (class "Default")
      (node (ref "IC1") (pin "38") (pinfunction "PL3(OC5A)_38") (pintype "bidirectional"))
    )
    (net (code "74") (name "D47") (class "Default")
      (node (ref "IC1") (pin "37") (pinfunction "PL2(T5)_37") (pintype "bidirectional"))
    )
    (net (code "75") (name "D48") (class "Default")
      (node (ref "IC1") (pin "36") (pinfunction "PL1(ICP5)_36") (pintype "bidirectional"))
    )
    (net (code "76") (name "D49") (class "Default")
      (node (ref "IC1") (pin "35") (pinfunction "PL0(ICP4)_35") (pintype "bidirectional"))
    )
    (net (code "77") (name "D50{slash}MISO") (class "Default")
      (node (ref "IC1") (pin "22") (pinfunction "(MISO/PCINT3)PB3_22") (pintype "bidirectional"))
      (node (ref "X1") (pin "7") (pinfunction "DATA_OUT_7") (pintype "output"))
    )
    (net (code "78") (name "D51{slash}MOSI") (class "Default")
      (node (ref "IC1") (pin "21") (pinfunction "(MOSI/PCINT2)PB2_21") (pintype "bidirectional"))
      (node (ref "IC5") (pin "5") (pinfunction "I_5") (pintype "input"))
    )
    (net (code "79") (name "D52{slash}SCK") (class "Default")
      (node (ref "IC1") (pin "20") (pinfunction "(SCK/PCINT1)PB1_20") (pintype "bidirectional"))
      (node (ref "IC5") (pin "3") (pinfunction "I_3") (pintype "input"))
      (node (ref "IC5") (pin "9") (pinfunction "I_9") (pintype "input"))
    )
    (net (code "80") (name "D53{slash}SS") (class "Default")
      (node (ref "IC1") (pin "19") (pinfunction "(SS/PCINT0)PB0_19") (pintype "bidirectional"))
      (node (ref "IC5") (pin "7") (pinfunction "I_7") (pintype "input"))
    )
    (net (code "81") (name "GND") (class "Default")
      (node (ref "B1") (pin "-") (pinfunction "-_-") (pintype "passive"))
      (node (ref "B2") (pin "-") (pinfunction "-_-") (pintype "passive"))
      (node (ref "BT3") (pin "GND@1") (pinfunction "-_GND@1") (pintype "power_in"))
      (node (ref "C1") (pin "2") (pinfunction "P$2_2") (pintype "passive"))
      (node (ref "C10") (pin "1") (pinfunction "P$1_1") (pintype "passive"))
      (node (ref "C13") (pin "1") (pinfunction "P$1_1") (pintype "passive"))
      (node (ref "C14") (pin "1") (pinfunction "P$1_1") (pintype "passive"))
      (node (ref "C15") (pin "1") (pinfunction "P$1_1") (pintype "passive"))
      (node (ref "C16") (pin "1") (pinfunction "P$1_1") (pintype "passive"))
      (node (ref "C17") (pin "1") (pinfunction "P$1_1") (pintype "passive"))
      (node (ref "C18") (pin "1") (pinfunction "P$1_1") (pintype "passive"))
      (node (ref "C2") (pin "2") (pinfunction "P$2_2") (pintype "passive"))
      (node (ref "C21") (pin "2") (pinfunction "P$2_2") (pintype "passive"))
      (node (ref "C22") (pin "2") (pinfunction "P$2_2") (pintype "passive"))
      (node (ref "C23") (pin "1") (pinfunction "P$1_1") (pintype "passive"))
      (node (ref "C24") (pin "1") (pinfunction "P$1_1") (pintype "passive"))
      (node (ref "C25") (pin "1") (pinfunction "P$1_1") (pintype "passive"))
      (node (ref "C26") (pin "1") (pinfunction "P$1_1") (pintype "passive"))
      (node (ref "C27") (pin "1") (pinfunction "P$1_1") (pintype "passive"))
      (node (ref "C28") (pin "1") (pinfunction "1_1") (pintype "passive"))
      (node (ref "C29") (pin "1") (pinfunction "1_1") (pintype "passive"))
      (node (ref "C3") (pin "2") (pinfunction "P$2_2") (pintype "passive"))
      (node (ref "C4") (pin "2") (pinfunction "P$2_2") (pintype "passive"))
      (node (ref "C5") (pin "-") (pinfunction "-_-") (pintype "passive"))
      (node (ref "C6") (pin "-") (pinfunction "-_-") (pintype "passive"))
      (node (ref "C8") (pin "1") (pinfunction "P$1_1") (pintype "passive"))
      (node (ref "C9") (pin "1") (pinfunction "1_1") (pintype "passive"))
      (node (ref "CN2") (pin "GND") (pinfunction "GND_GND") (pintype "power_in"))
      (node (ref "D6") (pin "1") (pinfunction "A_1") (pintype "passive"))
      (node (ref "D7") (pin "1") (pinfunction "A_1") (pintype "passive"))
      (node (ref "D8") (pin "1") (pinfunction "A_1") (pintype "passive"))
      (node (ref "D9") (pin "1") (pinfunction "A_1") (pintype "passive"))
      (node (ref "IC1") (pin "11") (pinfunction "GND_11") (pintype "power_in"))
      (node (ref "IC1") (pin "32") (pinfunction "GND1_32") (pintype "power_in"))
      (node (ref "IC1") (pin "62") (pinfunction "GND2_62") (pintype "power_in"))
      (node (ref "IC1") (pin "81") (pinfunction "GND3_81") (pintype "power_in"))
      (node (ref "IC1") (pin "99") (pinfunction "AGND_99") (pintype "power_in"))
      (node (ref "IC2") (pin "4") (pinfunction "VSS_4") (pintype "power_in"))
      (node (ref "IC3") (pin "3") (pinfunction "GND_3") (pintype "passive"))
      (node (ref "IC4") (pin "P$3") (pinfunction "GND_P$3") (pintype "power_in"))
      (node (ref "IC5") (pin "11") (pinfunction "I_11") (pintype "input"))
      (node (ref "IC5") (pin "14") (pinfunction "I_14") (pintype "input"))
      (node (ref "IC5") (pin "8") (pinfunction "VSS_8") (pintype "power_in"))
      (node (ref "IC6") (pin "2") (pinfunction "GND_2") (pintype "bidirectional"))
      (node (ref "IC7") (pin "3") (pinfunction "GND_3") (pintype "passive"))
      (node (ref "ICSP") (pin "6") (pinfunction "6_6") (pintype "bidirectional"))
      (node (ref "LED1") (pin "C") (pinfunction "C_C") (pintype "passive"))
      (node (ref "LED2") (pin "C") (pinfunction "C_C") (pintype "passive"))
      (node (ref "R17") (pin "2") (pinfunction "2_2") (pintype "passive"))
      (node (ref "R18") (pin "2") (pinfunction "2_2") (pintype "passive"))
      (node (ref "R19") (pin "2") (pinfunction "2_2") (pintype "passive"))
      (node (ref "R26") (pin "1") (pinfunction "1_1") (pintype "passive"))
      (node (ref "S1") (pin "1") (pinfunction "1_1") (pintype "passive"))
      (node (ref "S1") (pin "2") (pinfunction "2_2") (pintype "passive"))
      (node (ref "U$70") (pin "10") (pinfunction "PIN10(GND)_10") (pintype "bidirectional"))
      (node (ref "U$70") (pin "15") (pinfunction "PIN15(GND)_15") (pintype "bidirectional"))
      (node (ref "U$70") (pin "16") (pinfunction "PIN16(GND)_16") (pintype "bidirectional"))
      (node (ref "U$70") (pin "18") (pinfunction "COM2(GND)_18") (pintype "bidirectional"))
      (node (ref "U$70") (pin "2") (pinfunction "GND_2") (pintype "power_in"))
      (node (ref "U$70") (pin "25") (pinfunction "GND_25") (pintype "power_in"))
      (node (ref "U$78") (pin "P$1") (pinfunction "GND_P$1") (pintype "bidirectional"))
      (node (ref "U$78") (pin "P$2") (pinfunction "GND_P$2") (pintype "bidirectional"))
      (node (ref "U$84") (pin "1") (pinfunction "1_1") (pintype "bidirectional"))
      (node (ref "U$86") (pin "1") (pinfunction "1_1") (pintype "bidirectional"))
      (node (ref "U$87") (pin "1") (pinfunction "1_1") (pintype "bidirectional"))
      (node (ref "U$90") (pin "1") (pinfunction "1_1") (pintype "bidirectional"))
      (node (ref "U1") (pin "18") (pinfunction "GND2_18") (pintype "power_in"))
      (node (ref "U1") (pin "21") (pinfunction "GND3_21") (pintype "power_in"))
      (node (ref "U1") (pin "25") (pinfunction "AGND_25") (pintype "power_in"))
      (node (ref "U1") (pin "7") (pinfunction "GND1_7") (pintype "power_in"))
      (node (ref "U2") (pin "2") (pinfunction "GND_2") (pintype "power_in"))
      (node (ref "U3") (pin "2") (pinfunction "GND_2") (pintype "power_in"))
      (node (ref "U4") (pin "P$12") (pinfunction "GND_P$12") (pintype "bidirectional"))
      (node (ref "U4") (pin "P$19") (pinfunction "GND_P$19") (pintype "bidirectional"))
      (node (ref "U4") (pin "P$3") (pinfunction "GND_P$3") (pintype "bidirectional"))
      (node (ref "U4") (pin "P$8") (pinfunction "GND_P$8") (pintype "bidirectional"))
      (node (ref "U5") (pin "2") (pinfunction "GND_2") (pintype "power_in"))
      (node (ref "X1") (pin "6") (pinfunction "VSS_6") (pintype "power_in"))
      (node (ref "X1") (pin "MT1") (pinfunction "GND_MT1") (pintype "power_in"))
      (node (ref "X1") (pin "MT2") (pinfunction "GND1_MT2") (pintype "power_in"))
      (node (ref "XB1") (pin "10") (pinfunction "GND_10") (pintype "power_in"))
    )
    (net (code "82") (name "Net-(B2-+-Pad+$1)") (class "Default")
      (node (ref "B2") (pin "+$1") (pinfunction "+_+$1") (pintype "passive"))
      (node (ref "B2") (pin "+$2") (pinfunction "+_+$2") (pintype "passive"))
      (node (ref "D5") (pin "A") (pinfunction "A_A") (pintype "passive"))
    )
    (net (code "83") (name "Net-(BT1-+)") (class "Default")
      (node (ref "BT1") (pin "PWR@1") (pinfunction "+_PWR@1") (pintype "power_in"))
      (node (ref "D1") (pin "A") (pinfunction "A_A") (pintype "passive"))
    )
    (net (code "84") (name "Net-(BT1--)") (class "Default")
      (node (ref "BT1") (pin "GND@1") (pinfunction "-_GND@1") (pintype "power_in"))
      (node (ref "BT2") (pin "PWR@1") (pinfunction "+_PWR@1") (pintype "power_in"))
    )
    (net (code "85") (name "Net-(BT2--)") (class "Default")
      (node (ref "BT2") (pin "GND@1") (pinfunction "-_GND@1") (pintype "power_in"))
      (node (ref "BT3") (pin "PWR@1") (pinfunction "+_PWR@1") (pintype "power_in"))
    )
    (net (code "86") (name "Net-(BT4--)") (class "Default")
      (node (ref "BT4") (pin "GND@1") (pinfunction "-_GND@1") (pintype "power_in"))
      (node (ref "BT5") (pin "PWR@1") (pinfunction "+_PWR@1") (pintype "power_in"))
    )
    (net (code "87") (name "Net-(BT5--)") (class "Default")
      (node (ref "BT5") (pin "GND@1") (pinfunction "-_GND@1") (pintype "power_in"))
      (node (ref "BT6") (pin "PWR@1") (pinfunction "+_PWR@1") (pintype "power_in"))
    )
    (net (code "88") (name "Net-(C7-P$1)") (class "Default")
      (node (ref "C7") (pin "1") (pinfunction "P$1_1") (pintype "passive"))
      (node (ref "U1") (pin "2") (pinfunction "DTR_2") (pintype "bidirectional"))
    )
    (net (code "89") (name "Net-(C11-P$1)") (class "Default")
      (node (ref "C11") (pin "1") (pinfunction "P$1_1") (pintype "passive"))
      (node (ref "Y1") (pin "2") (pinfunction "2_2") (pintype "passive"))
    )
    (net (code "90") (name "Net-(C12-P$1)") (class "Default")
      (node (ref "C12") (pin "1") (pinfunction "P$1_1") (pintype "passive"))
      (node (ref "Y1") (pin "1") (pinfunction "1_1") (pintype "passive"))
    )
    (net (code "91") (name "Net-(C14-P$2)") (class "Default")
      (node (ref "C14") (pin "2") (pinfunction "P$2_2") (pintype "passive"))
      (node (ref "IC2") (pin "8") (pinfunction "VDD_8") (pintype "power_in"))
      (node (ref "R1") (pin "2") (pinfunction "2_2") (pintype "passive"))
    )
    (net (code "92") (name "Net-(C17-P$2)") (class "Default")
      (node (ref "C17") (pin "2") (pinfunction "P$2_2") (pintype "passive"))
      (node (ref "IC4") (pin "P$2") (pinfunction "CAP_P$2") (pintype "passive"))
    )
    (net (code "93") (name "Net-(C22-P$1)") (class "Default")
      (node (ref "C22") (pin "1") (pinfunction "P$1_1") (pintype "passive"))
      (node (ref "U$70") (pin "9") (pinfunction "CAP_9") (pintype "passive"))
    )
    (net (code "94") (name "Net-(C23-P$2)") (class "Default")
      (node (ref "C23") (pin "2") (pinfunction "P$2_2") (pintype "passive"))
      (node (ref "U$70") (pin "26") (pinfunction "XOUT32_26") (pintype "output"))
      (node (ref "Y2") (pin "P$1") (pinfunction "1_P$1") (pintype "passive"))
    )
    (net (code "95") (name "Net-(C24-P$2)") (class "Default")
      (node (ref "C24") (pin "2") (pinfunction "P$2_2") (pintype "passive"))
      (node (ref "U$70") (pin "27") (pinfunction "XIN32_27") (pintype "input"))
      (node (ref "Y2") (pin "P$4") (pinfunction "2_P$4") (pintype "passive"))
    )
    (net (code "96") (name "Net-(FB1-P$2)") (class "Default")
      (node (ref "FB1") (pin "2") (pinfunction "P$2_2") (pintype "passive"))
      (node (ref "R27") (pin "2") (pinfunction "2_2") (pintype "passive"))
      (node (ref "U4") (pin "P$1") (pinfunction "VCC_P$1") (pintype "bidirectional"))
    )
    (net (code "97") (name "Net-(IC2-VBAT)") (class "Default")
      (node (ref "B1") (pin "+$1") (pinfunction "+_+$1") (pintype "passive"))
      (node (ref "B1") (pin "+$2") (pinfunction "+_+$2") (pintype "passive"))
      (node (ref "IC2") (pin "3") (pinfunction "VBAT_3") (pintype "power_in"))
    )
    (net (code "98") (name "Net-(IC2-XI)") (class "Default")
      (node (ref "IC2") (pin "1") (pinfunction "XI_1") (pintype "input"))
      (node (ref "Q1") (pin "P$1") (pinfunction "1_P$1") (pintype "passive"))
    )
    (net (code "99") (name "Net-(IC2-XO)") (class "Default")
      (node (ref "IC2") (pin "2") (pinfunction "XO_2") (pintype "output"))
      (node (ref "Q1") (pin "P$4") (pinfunction "2_P$4") (pintype "passive"))
    )
    (net (code "100") (name "Net-(IC3-VO)") (class "Default")
      (node (ref "IC3") (pin "2") (pinfunction "VO_2") (pintype "passive"))
      (node (ref "XB1") (pin "1") (pinfunction "VCC_1") (pintype "power_in"))
    )
    (net (code "101") (name "Net-(IC5A-O)") (class "Default")
      (node (ref "IC5") (pin "2") (pinfunction "O_2") (pintype "output"))
      (node (ref "X1") (pin "5") (pinfunction "SCLK_5") (pintype "input"))
    )
    (net (code "102") (name "Net-(IC5B-O)") (class "Default")
      (node (ref "IC5") (pin "4") (pinfunction "O_4") (pintype "output"))
      (node (ref "X1") (pin "3") (pinfunction "DATA_IN_3") (pintype "input"))
    )
    (net (code "103") (name "Net-(IC5C-O)") (class "Default")
      (node (ref "IC5") (pin "6") (pinfunction "O_6") (pintype "output"))
      (node (ref "R16") (pin "2") (pinfunction "2_2") (pintype "passive"))
      (node (ref "X1") (pin "2") (pinfunction "CS_2") (pintype "input"))
    )
    (net (code "104") (name "Net-(IC5D-O)") (class "Default")
      (node (ref "IC5") (pin "10") (pinfunction "O_10") (pintype "output"))
      (node (ref "LED5") (pin "A") (pinfunction "A_A") (pintype "passive"))
    )
    (net (code "105") (name "Net-(IC5G-VDD)") (class "Default")
      (node (ref "C29") (pin "2") (pinfunction "2_2") (pintype "passive"))
      (node (ref "C9") (pin "2") (pinfunction "2_2") (pintype "passive"))
      (node (ref "IC5") (pin "1") (pinfunction "VDD_1") (pintype "power_in"))
      (node (ref "IC6") (pin "5") (pinfunction "VOUT_5") (pintype "bidirectional"))
      (node (ref "X1") (pin "4") (pinfunction "VDD_4") (pintype "power_in"))
    )
    (net (code "106") (name "Net-(IGNITER_1-Pad2)") (class "Default")
      (node (ref "IGNITER_1") (pin "2") (pinfunction "2_2") (pintype "passive"))
      (node (ref "U$87") (pin "NC") (pinfunction "NC_NC") (pintype "bidirectional"))
    )
    (net (code "107") (name "Net-(IGNITER_2-Pad2)") (class "Default")
      (node (ref "IGNITER_2") (pin "2") (pinfunction "2_2") (pintype "passive"))
      (node (ref "U$84") (pin "NC") (pinfunction "NC_NC") (pintype "bidirectional"))
    )
    (net (code "108") (name "Net-(IGNITER_3-Pad2)") (class "Default")
      (node (ref "IGNITER_3") (pin "2") (pinfunction "2_2") (pintype "passive"))
      (node (ref "U$86") (pin "NC") (pinfunction "NC_NC") (pintype "bidirectional"))
    )
    (net (code "109") (name "Net-(IGNITER_4-Pad2)") (class "Default")
      (node (ref "IGNITER_4") (pin "2") (pinfunction "2_2") (pintype "passive"))
      (node (ref "U$90") (pin "NC") (pinfunction "NC_NC") (pintype "bidirectional"))
    )
    (net (code "110") (name "Net-(LED1-PadA)") (class "Default")
      (node (ref "LED1") (pin "A") (pinfunction "A_A") (pintype "passive"))
      (node (ref "R4") (pin "1") (pinfunction "1_1") (pintype "passive"))
    )
    (net (code "111") (name "Net-(LED2-PadA)") (class "Default")
      (node (ref "LED2") (pin "A") (pinfunction "A_A") (pintype "passive"))
      (node (ref "R5") (pin "1") (pinfunction "1_1") (pintype "passive"))
    )
    (net (code "112") (name "Net-(LED3-PadC)") (class "Default")
      (node (ref "LED3") (pin "C") (pinfunction "C_C") (pintype "passive"))
      (node (ref "R8") (pin "1") (pinfunction "1_1") (pintype "passive"))
    )
    (net (code "113") (name "Net-(LED4-PadC)") (class "Default")
      (node (ref "LED4") (pin "C") (pinfunction "C_C") (pintype "passive"))
      (node (ref "R9") (pin "1") (pinfunction "1_1") (pintype "passive"))
    )
    (net (code "114") (name "Net-(LED5-PadC)") (class "Default")
      (node (ref "LED5") (pin "C") (pinfunction "C_C") (pintype "passive"))
      (node (ref "R16") (pin "1") (pinfunction "1_1") (pintype "passive"))
    )
    (net (code "115") (name "Net-(LED6-PadC)") (class "Default")
      (node (ref "LED6") (pin "C") (pinfunction "C_C") (pintype "passive"))
      (node (ref "R26") (pin "2") (pinfunction "2_2") (pintype "passive"))
    )
    (net (code "116") (name "Net-(U$70-PS0)") (class "Default")
      (node (ref "R18") (pin "1") (pinfunction "1_1") (pintype "passive"))
      (node (ref "U$70") (pin "6") (pinfunction "PS0_6") (pintype "input"))
    )
    (net (code "117") (name "Net-(U$70-PS1)") (class "Default")
      (node (ref "R19") (pin "1") (pinfunction "1_1") (pintype "passive"))
      (node (ref "U$70") (pin "5") (pinfunction "PS1_5") (pintype "input"))
    )
    (net (code "118") (name "Net-(U$78-SIGNAL)") (class "Default")
      (node (ref "U$78") (pin "P$3") (pinfunction "SIGNAL_P$3") (pintype "bidirectional"))
      (node (ref "U4") (pin "P$11") (pinfunction "EX_ANT_P$11") (pintype "bidirectional"))
    )
    (net (code "119") (name "Net-(U1-RXLED)") (class "Default")
      (node (ref "R9") (pin "2") (pinfunction "2_2") (pintype "passive"))
      (node (ref "U1") (pin "22") (pinfunction "RXLED_22") (pintype "bidirectional"))
    )
    (net (code "120") (name "Net-(U1-TXLED)") (class "Default")
      (node (ref "R8") (pin "2") (pinfunction "2_2") (pintype "passive"))
      (node (ref "U1") (pin "23") (pinfunction "TXLED_23") (pintype "bidirectional"))
    )
    (net (code "121") (name "Net-(U1-USB+)") (class "Default")
      (node (ref "CN2") (pin "D+") (pinfunction "D+_D+") (pintype "bidirectional"))
      (node (ref "U1") (pin "15") (pinfunction "USB+_15") (pintype "bidirectional"))
    )
    (net (code "122") (name "Net-(U1-USB-)") (class "Default")
      (node (ref "CN2") (pin "D-") (pinfunction "D-_D-") (pintype "bidirectional"))
      (node (ref "U1") (pin "16") (pinfunction "USB-_16") (pintype "bidirectional"))
    )
    (net (code "123") (name "Net-(U4-3D-FIX)") (class "Default")
      (node (ref "LED6") (pin "A") (pinfunction "A_A") (pintype "passive"))
      (node (ref "U4") (pin "P$5") (pinfunction "3D-FIX_P$5") (pintype "bidirectional"))
    )
    (net (code "124") (name "Net-(U4-RX)") (class "Default")
      (node (ref "D4") (pin "A") (pinfunction "A_A") (pintype "passive"))
      (node (ref "R27") (pin "1") (pinfunction "1_1") (pintype "passive"))
      (node (ref "U4") (pin "P$10") (pinfunction "RX_P$10") (pintype "bidirectional"))
    )
    (net (code "125") (name "Net-(U4-VBACKUP)") (class "Default")
      (node (ref "D5") (pin "C") (pinfunction "C_C") (pintype "passive"))
      (node (ref "U4") (pin "P$4") (pinfunction "VBACKUP_P$4") (pintype "bidirectional"))
    )
    (net (code "126") (name "Net-(U5-EN)") (class "Default")
      (node (ref "R25") (pin "1") (pinfunction "1_1") (pintype "passive"))
      (node (ref "U5") (pin "3") (pinfunction "EN_3") (pintype "input"))
    )
    (net (code "127") (name "PB1") (class "Default")
      (node (ref "ICSP") (pin "3") (pinfunction "3_3") (pintype "bidirectional"))
    )
    (net (code "128") (name "PB2") (class "Default")
      (node (ref "ICSP") (pin "4") (pinfunction "4_4") (pintype "bidirectional"))
    )
    (net (code "129") (name "PB3") (class "Default")
      (node (ref "ICSP") (pin "1") (pinfunction "1_1") (pintype "bidirectional"))
    )
    (net (code "130") (name "PB7") (class "Default")
      (node (ref "R5") (pin "2") (pinfunction "2_2") (pintype "passive"))
    )
    (net (code "131") (name "RESET") (class "Default")
      (node (ref "C4") (pin "1") (pinfunction "P$1_1") (pintype "passive"))
      (node (ref "C7") (pin "2") (pinfunction "P$2_2") (pintype "passive"))
      (node (ref "IC1") (pin "30") (pinfunction "RESET_30") (pintype "input"))
      (node (ref "ICSP") (pin "5") (pinfunction "5_5") (pintype "bidirectional"))
      (node (ref "R3") (pin "1") (pinfunction "1_1") (pintype "passive"))
      (node (ref "S1") (pin "3") (pinfunction "3_3") (pintype "passive"))
      (node (ref "S1") (pin "4") (pinfunction "4_4") (pintype "passive"))
    )
    (net (code "132") (name "RXD1") (class "Default")
      (node (ref "IC1") (pin "45") (pinfunction "(RXD1/INT2)PD2_45") (pintype "bidirectional"))
    )
    (net (code "133") (name "RXD2") (class "Default")
      (node (ref "IC1") (pin "12") (pinfunction "PH0(RXD2)_12") (pintype "bidirectional"))
    )
    (net (code "134") (name "SCL") (class "Default")
      (node (ref "IC1") (pin "43") (pinfunction "(SCL/INT0)PD0_43") (pintype "bidirectional"))
      (node (ref "IC2") (pin "6") (pinfunction "SCL_6") (pintype "bidirectional"))
      (node (ref "Q2") (pin "3") (pinfunction "D_3") (pintype "bidirectional"))
      (node (ref "Q5") (pin "3") (pinfunction "D_3") (pintype "bidirectional"))
      (node (ref "R10") (pin "2") (pinfunction "2_2") (pintype "passive"))
      (node (ref "R13") (pin "2") (pinfunction "2_2") (pintype "passive"))
      (node (ref "R24") (pin "1") (pinfunction "1_1") (pintype "passive"))
      (node (ref "R6") (pin "1") (pinfunction "1_1") (pintype "passive"))
    )
    (net (code "135") (name "SDA") (class "Default")
      (node (ref "IC1") (pin "44") (pinfunction "(SDA/INT1)PD1_44") (pintype "bidirectional"))
      (node (ref "IC2") (pin "5") (pinfunction "SDA_5") (pintype "bidirectional"))
      (node (ref "Q3") (pin "3") (pinfunction "D_3") (pintype "bidirectional"))
      (node (ref "Q4") (pin "3") (pinfunction "D_3") (pintype "bidirectional"))
      (node (ref "R11") (pin "2") (pinfunction "2_2") (pintype "passive"))
      (node (ref "R15") (pin "1") (pinfunction "1_1") (pintype "passive"))
      (node (ref "R23") (pin "1") (pinfunction "1_1") (pintype "passive"))
      (node (ref "R7") (pin "1") (pinfunction "1_1") (pintype "passive"))
    )
    (net (code "136") (name "SPARKGAP+") (class "Default")
      (node (ref "BT4") (pin "PWR@1") (pinfunction "+_PWR@1") (pintype "power_in"))
      (node (ref "U$84") (pin "NO") (pinfunction "NO_NO") (pintype "bidirectional"))
      (node (ref "U$86") (pin "NO") (pinfunction "NO_NO") (pintype "bidirectional"))
      (node (ref "U$87") (pin "NO") (pinfunction "NO_NO") (pintype "bidirectional"))
      (node (ref "U$90") (pin "NO") (pinfunction "NO_NO") (pintype "bidirectional"))
    )
    (net (code "137") (name "SPARKGAP-") (class "Default")
      (node (ref "BT6") (pin "GND@1") (pinfunction "-_GND@1") (pintype "power_in"))
      (node (ref "IGNITER_1") (pin "1") (pinfunction "1_1") (pintype "passive"))
      (node (ref "IGNITER_2") (pin "1") (pinfunction "1_1") (pintype "passive"))
      (node (ref "IGNITER_3") (pin "1") (pinfunction "1_1") (pintype "passive"))
      (node (ref "IGNITER_4") (pin "1") (pinfunction "1_1") (pintype "passive"))
    )
    (net (code "138") (name "TXD1") (class "Default")
      (node (ref "IC1") (pin "46") (pinfunction "(TXD1/INT3)PD3_46") (pintype "bidirectional"))
    )
    (net (code "139") (name "TXD2") (class "Default")
      (node (ref "IC1") (pin "13") (pinfunction "PH1(TXD2)_13") (pintype "bidirectional"))
    )
    (net (code "140") (name "VIN") (class "Default")
      (node (ref "C5") (pin "+") (pinfunction "+_+") (pintype "passive"))
      (node (ref "D1") (pin "C") (pinfunction "C_C") (pintype "passive"))
      (node (ref "IC3") (pin "1") (pinfunction "VI_1") (pintype "input"))
      (node (ref "IC7") (pin "1") (pinfunction "VI_1") (pintype "input"))
    )
    (net (code "141") (name "VUSB") (class "Default")
      (node (ref "C10") (pin "2") (pinfunction "P$2_2") (pintype "passive"))
      (node (ref "C28") (pin "2") (pinfunction "2_2") (pintype "passive"))
      (node (ref "CN2") (pin "VBUS") (pinfunction "VBUS_VBUS") (pintype "power_in"))
      (node (ref "D2") (pin "A") (pinfunction "A_A") (pintype "passive"))
    )
    (net (code "142") (name "unconnected-(CN2-PadID)") (class "Default")
      (node (ref "CN2") (pin "ID") (pinfunction "ID_ID") (pintype "bidirectional"))
    )
    (net (code "143") (name "unconnected-(IC1-(CLKO{slash}ICP3{slash}INT7)PE7-Pad9)") (class "Default")
      (node (ref "IC1") (pin "9") (pinfunction "(CLKO/ICP3/INT7)PE7_9") (pintype "bidirectional"))
    )
    (net (code "144") (name "unconnected-(IC1-(ICP1)PD4-Pad47)") (class "Default")
      (node (ref "IC1") (pin "47") (pinfunction "(ICP1)PD4_47") (pintype "bidirectional"))
    )
    (net (code "145") (name "unconnected-(IC1-(T1)PD6-Pad49)") (class "Default")
      (node (ref "IC1") (pin "49") (pinfunction "(T1)PD6_49") (pintype "bidirectional"))
    )
    (net (code "146") (name "unconnected-(IC1-(T3{slash}INT6)PE6-Pad8)") (class "Default")
      (node (ref "IC1") (pin "8") (pinfunction "(T3/INT6)PE6_8") (pintype "bidirectional"))
    )
    (net (code "147") (name "unconnected-(IC1-(TOSC1)PG4-Pad29)") (class "Default")
      (node (ref "IC1") (pin "29") (pinfunction "(TOSC1)PG4_29") (pintype "bidirectional"))
    )
    (net (code "148") (name "unconnected-(IC1-(TOSC2)PG3-Pad28)") (class "Default")
      (node (ref "IC1") (pin "28") (pinfunction "(TOSC2)PG3_28") (pintype "bidirectional"))
    )
    (net (code "149") (name "unconnected-(IC1-(XCK0{slash}AIN0)PE2-Pad4)") (class "Default")
      (node (ref "IC1") (pin "4") (pinfunction "(XCK0/AIN0)PE2_4") (pintype "bidirectional"))
    )
    (net (code "150") (name "unconnected-(IC1-(XCK1)PD5-Pad48)") (class "Default")
      (node (ref "IC1") (pin "48") (pinfunction "(XCK1)PD5_48") (pintype "bidirectional"))
    )
    (net (code "151") (name "unconnected-(IC1-PH2(XCK2)-Pad14)") (class "Default")
      (node (ref "IC1") (pin "14") (pinfunction "PH2(XCK2)_14") (pintype "bidirectional"))
    )
    (net (code "152") (name "unconnected-(IC1-PH7(T4)-Pad27)") (class "Default")
      (node (ref "IC1") (pin "27") (pinfunction "PH7(T4)_27") (pintype "bidirectional"))
    )
    (net (code "153") (name "unconnected-(IC1-PJ2(XCK3{slash}PCINT11)-Pad65)") (class "Default")
      (node (ref "IC1") (pin "65") (pinfunction "PJ2(XCK3/PCINT11)_65") (pintype "bidirectional"))
    )
    (net (code "154") (name "unconnected-(IC1-PJ3(PCINT12)-Pad66)") (class "Default")
      (node (ref "IC1") (pin "66") (pinfunction "PJ3(PCINT12)_66") (pintype "bidirectional"))
    )
    (net (code "155") (name "unconnected-(IC1-PJ4(PCINT13)-Pad67)") (class "Default")
      (node (ref "IC1") (pin "67") (pinfunction "PJ4(PCINT13)_67") (pintype "bidirectional"))
    )
    (net (code "156") (name "unconnected-(IC1-PJ5(PCINT14)-Pad68)") (class "Default")
      (node (ref "IC1") (pin "68") (pinfunction "PJ5(PCINT14)_68") (pintype "bidirectional"))
    )
    (net (code "157") (name "unconnected-(IC1-PJ6(PCINT15)-Pad69)") (class "Default")
      (node (ref "IC1") (pin "69") (pinfunction "PJ6(PCINT15)_69") (pintype "bidirectional"))
    )
    (net (code "158") (name "unconnected-(IC1-PJ7-Pad79)") (class "Default")
      (node (ref "IC1") (pin "79") (pinfunction "PJ7_79") (pintype "bidirectional"))
    )
    (net (code "159") (name "unconnected-(IC4-INT1-PadP$6)") (class "Default")
      (node (ref "IC4") (pin "P$6") (pinfunction "INT1_P$6") (pintype "output"))
    )
    (net (code "160") (name "unconnected-(IC4-INT2-PadP$5)") (class "Default")
      (node (ref "IC4") (pin "P$5") (pinfunction "INT2_P$5") (pintype "output"))
    )
    (net (code "161") (name "unconnected-(IC5E-O-Pad12)") (class "Default")
      (node (ref "IC5") (pin "12") (pinfunction "O_12") (pintype "output"))
    )
    (net (code "162") (name "unconnected-(IC5F-O-Pad15)") (class "Default")
      (node (ref "IC5") (pin "15") (pinfunction "O_15") (pintype "output"))
    )
    (net (code "163") (name "unconnected-(IC6-BYP-Pad4)") (class "Default")
      (node (ref "IC6") (pin "4") (pinfunction "BYP_4") (pintype "bidirectional"))
    )
    (net (code "164") (name "unconnected-(U$70-PIN7(SWDIO)-Pad7)") (class "Default")
      (node (ref "U$70") (pin "7") (pinfunction "PIN7(SWDIO)_7") (pintype "bidirectional"))
    )
    (net (code "165") (name "unconnected-(U$70-PIN8(SWCLK)-Pad8)") (class "Default")
      (node (ref "U$70") (pin "8") (pinfunction "PIN8(SWCLK)_8") (pintype "bidirectional"))
    )
    (net (code "166") (name "unconnected-(U$84-PadCOM)") (class "Default")
      (node (ref "U$84") (pin "COM") (pinfunction "COM_COM") (pintype "bidirectional"))
    )
    (net (code "167") (name "unconnected-(U$86-PadCOM)") (class "Default")
      (node (ref "U$86") (pin "COM") (pinfunction "COM_COM") (pintype "bidirectional"))
    )
    (net (code "168") (name "unconnected-(U$87-PadCOM)") (class "Default")
      (node (ref "U$87") (pin "COM") (pinfunction "COM_COM") (pintype "bidirectional"))
    )
    (net (code "169") (name "unconnected-(U$90-PadCOM)") (class "Default")
      (node (ref "U$90") (pin "COM") (pinfunction "COM_COM") (pintype "bidirectional"))
    )
    (net (code "170") (name "unconnected-(U1-CTS-Pad11)") (class "Default")
      (node (ref "U1") (pin "11") (pinfunction "CTS_11") (pintype "bidirectional"))
    )
    (net (code "171") (name "unconnected-(U1-RTS-Pad3)") (class "Default")
      (node (ref "U1") (pin "3") (pinfunction "RTS_3") (pintype "bidirectional"))
    )
    (net (code "172") (name "unconnected-(U1-TEST-Pad26)") (class "Default")
      (node (ref "U1") (pin "26") (pinfunction "TEST_26") (pintype "input"))
    )
    (net (code "173") (name "unconnected-(U2-P4-Pad4)") (class "Default")
      (node (ref "U2") (pin "4") (pinfunction "P4_4") (pintype "bidirectional"))
    )
    (net (code "174") (name "unconnected-(U3-P4-Pad4)") (class "Default")
      (node (ref "U3") (pin "4") (pinfunction "P4_4") (pintype "bidirectional"))
    )
    (net (code "175") (name "unconnected-(U4-1PPS-PadP$13)") (class "Default")
      (node (ref "U4") (pin "P$13") (pinfunction "1PPS_P$13") (pintype "bidirectional"))
    )
    (net (code "176") (name "unconnected-(U4-NC-PadP$6)") (class "Default")
      (node (ref "U4") (pin "P$6") (pinfunction "NC_P$6") (pintype "bidirectional"))
    )
    (net (code "177") (name "unconnected-(U4-NC-PadP$7)") (class "Default")
      (node (ref "U4") (pin "P$7") (pinfunction "NC_P$7") (pintype "bidirectional"))
    )
    (net (code "178") (name "unconnected-(U4-NC-PadP$15)") (class "Default")
      (node (ref "U4") (pin "P$15") (pinfunction "NC_P$15") (pintype "bidirectional"))
    )
    (net (code "179") (name "unconnected-(U4-NC-PadP$16)") (class "Default")
      (node (ref "U4") (pin "P$16") (pinfunction "NC_P$16") (pintype "bidirectional"))
    )
    (net (code "180") (name "unconnected-(U4-NC-PadP$17)") (class "Default")
      (node (ref "U4") (pin "P$17") (pinfunction "NC_P$17") (pintype "bidirectional"))
    )
    (net (code "181") (name "unconnected-(U4-NC-PadP$18)") (class "Default")
      (node (ref "U4") (pin "P$18") (pinfunction "NC_P$18") (pintype "bidirectional"))
    )
    (net (code "182") (name "unconnected-(U4-NC-PadP$20)") (class "Default")
      (node (ref "U4") (pin "P$20") (pinfunction "NC_P$20") (pintype "bidirectional"))
    )
    (net (code "183") (name "unconnected-(U4-NRESET-PadP$2)") (class "Default")
      (node (ref "U4") (pin "P$2") (pinfunction "NRESET_P$2") (pintype "bidirectional"))
    )
    (net (code "184") (name "unconnected-(U4-RTCM-PadP$14)") (class "Default")
      (node (ref "U4") (pin "P$14") (pinfunction "RTCM_P$14") (pintype "bidirectional"))
    )
    (net (code "185") (name "unconnected-(U5-P4-Pad4)") (class "Default")
      (node (ref "U5") (pin "4") (pinfunction "P4_4") (pintype "bidirectional"))
    )
    (net (code "186") (name "unconnected-(X1-CARD_DETECT1-PadCD2)") (class "Default")
      (node (ref "X1") (pin "CD2") (pinfunction "CARD_DETECT1_CD2") (pintype "passive"))
    )
    (net (code "187") (name "unconnected-(X1-DAT1-Pad8)") (class "Default")
      (node (ref "X1") (pin "8") (pinfunction "DAT1_8") (pintype "bidirectional"))
    )
    (net (code "188") (name "unconnected-(X1-DAT2-Pad1)") (class "Default")
      (node (ref "X1") (pin "1") (pinfunction "DAT2_1") (pintype "bidirectional"))
    )
    (net (code "189") (name "unconnected-(XB1-AD0{slash}DIO0-Pad20)") (class "Default")
      (node (ref "XB1") (pin "20") (pinfunction "AD0/DIO0_20") (pintype "bidirectional"))
    )
    (net (code "190") (name "unconnected-(XB1-AD1{slash}DIO1-Pad19)") (class "Default")
      (node (ref "XB1") (pin "19") (pinfunction "AD1/DIO1_19") (pintype "bidirectional"))
    )
    (net (code "191") (name "unconnected-(XB1-AD2{slash}DIO2-Pad18)") (class "Default")
      (node (ref "XB1") (pin "18") (pinfunction "AD2/DIO2_18") (pintype "bidirectional"))
    )
    (net (code "192") (name "unconnected-(XB1-ASSOC{slash}AD5{slash}DIO5-Pad15)") (class "Default")
      (node (ref "XB1") (pin "15") (pinfunction "ASSOC/AD5/DIO5_15") (pintype "bidirectional"))
    )
    (net (code "193") (name "unconnected-(XB1-CD{slash}DOUT_EN{slash}DO8-Pad4)") (class "Default")
      (node (ref "XB1") (pin "4") (pinfunction "CD/DOUT_EN/DO8_4") (pintype "output"))
    )
    (net (code "194") (name "unconnected-(XB1-COORD_SEL{slash}AD3{slash}DIO3-Pad17)") (class "Default")
      (node (ref "XB1") (pin "17") (pinfunction "COORD_SEL/AD3/DIO3_17") (pintype "bidirectional"))
    )
    (net (code "195") (name "unconnected-(XB1-ON{slash}~{SLEEP}-Pad13)") (class "Default")
      (node (ref "XB1") (pin "13") (pinfunction "ON/~{SLEEP}_13") (pintype "output"))
    )
    (net (code "196") (name "unconnected-(XB1-PWM0{slash}RSSI-Pad6)") (class "Default")
      (node (ref "XB1") (pin "6") (pinfunction "PWM0/RSSI_6") (pintype "output"))
    )
    (net (code "197") (name "unconnected-(XB1-RF_TX{slash}AD4{slash}DIO4-Pad11)") (class "Default")
      (node (ref "XB1") (pin "11") (pinfunction "RF_TX/AD4/DIO4_11") (pintype "bidirectional"))
    )
    (net (code "198") (name "unconnected-(XB1-VREF-Pad14)") (class "Default")
      (node (ref "XB1") (pin "14") (pinfunction "VREF_14") (pintype "input"))
    )
    (net (code "199") (name "unconnected-(XB1-~{CTS}{slash}DIO7-Pad12)") (class "Default")
      (node (ref "XB1") (pin "12") (pinfunction "~{CTS}/DIO7_12") (pintype "bidirectional"))
    )
    (net (code "200") (name "unconnected-(XB1-~{DTR}{slash}SLEEP_RQ{slash}DI8-Pad9)") (class "Default")
      (node (ref "XB1") (pin "9") (pinfunction "~{DTR}/SLEEP_RQ/DI8_9") (pintype "bidirectional"))
    )
    (net (code "201") (name "unconnected-(XB1-~{RESET}-Pad5)") (class "Default")
      (node (ref "XB1") (pin "5") (pinfunction "~{RESET}_5") (pintype "input"))
    )
    (net (code "202") (name "unconnected-(XB1-~{RTS}{slash}AD6{slash}DIO6-Pad16)") (class "Default")
      (node (ref "XB1") (pin "16") (pinfunction "~{RTS}/AD6/DIO6_16") (pintype "bidirectional"))
    )
  )
)
